# charger.net
KiCad netlist of a schematic drawn in EAGLE
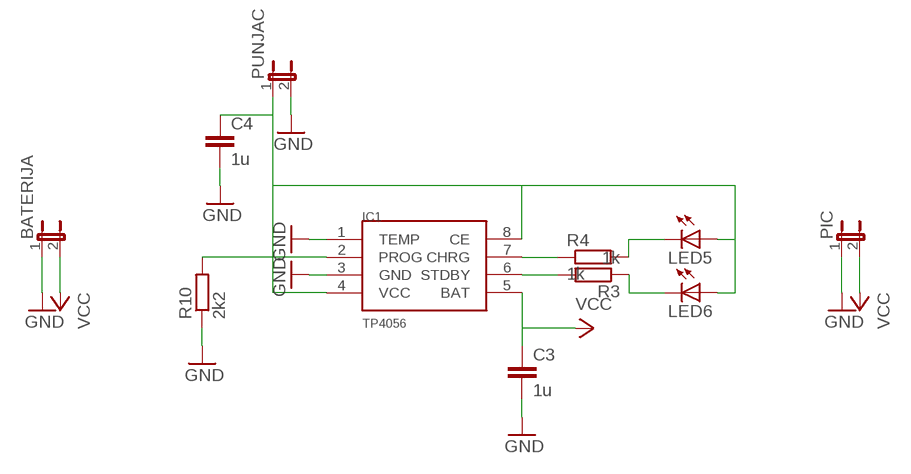
[diagram p0: schematic, sheet 1]

(export (version "E")
  (design (tool "Eeschema 10.0.6"))
  (components
    (comp (ref "BATERIJA")
      (value "JP1E")
      (footprint "eagle-import:JP1")
      (libsource (lib "eagle-import") (part "JP1E"))
    )
    (comp (ref "C3")
      (value "1u")
      (footprint "eagle-import:C050-024X044")
      (libsource (lib "eagle-import") (part "C-EU050-024X044"))
    )
    (comp (ref "C4")
      (value "1u")
      (footprint "eagle-import:C050-024X044")
      (libsource (lib "eagle-import") (part "C-EU050-024X044"))
    )
    (comp (ref "IC1")
      (value "TP4056")
      (footprint "eagle-import:SOP-8")
      (libsource (lib "eagle-import") (part "TP4056"))
    )
    (comp (ref "LED5")
      (value "LED3MM")
      (footprint "eagle-import:LED3MM")
      (libsource (lib "eagle-import") (part "LED3MM"))
    )
    (comp (ref "LED6")
      (value "LED3MM")
      (footprint "eagle-import:LED3MM")
      (libsource (lib "eagle-import") (part "LED3MM"))
    )
    (comp (ref "PIC")
      (value "JP1E")
      (footprint "eagle-import:JP1")
      (libsource (lib "eagle-import") (part "JP1E"))
    )
    (comp (ref "PUNJAC")
      (value "JP1E")
      (footprint "eagle-import:JP1")
      (libsource (lib "eagle-import") (part "JP1E"))
    )
    (comp (ref "R3")
      (value "1k")
      (footprint "eagle-import:0207_10")
      (libsource (lib "eagle-import") (part "R-EU_0207/10"))
    )
    (comp (ref "R4")
      (value "1k")
      (footprint "eagle-import:0207_10")
      (libsource (lib "eagle-import") (part "R-EU_0207/10"))
    )
    (comp (ref "R10")
      (value "2k2")
      (footprint "eagle-import:0207_10")
      (libsource (lib "eagle-import") (part "R-EU_0207/10"))
    )
  )
  (nets
    (net (code "1") (name "GND") (class "Default")
      (node (ref "BATERIJA") (pin "1") (pinfunction "1_1") (pintype "passive"))
      (node (ref "C3") (pin "2") (pinfunction "2_2") (pintype "passive"))
      (node (ref "C4") (pin "2") (pinfunction "2_2") (pintype "passive"))
      (node (ref "IC1") (pin "1") (pinfunction "TEMP_1") (pintype "bidirectional"))
      (node (ref "IC1") (pin "3") (pinfunction "GND_3") (pintype "bidirectional"))
      (node (ref "PIC") (pin "1") (pinfunction "1_1") (pintype "passive"))
      (node (ref "PUNJAC") (pin "2") (pinfunction "2_2") (pintype "passive"))
      (node (ref "R10") (pin "1") (pinfunction "1_1") (pintype "passive"))
    )
    (net (code "2") (name "Net-(IC1-CE)") (class "Default")
      (node (ref "C4") (pin "1") (pinfunction "1_1") (pintype "passive"))
      (node (ref "IC1") (pin "4") (pinfunction "VCC_4") (pintype "bidirectional"))
      (node (ref "IC1") (pin "8") (pinfunction "CE_8") (pintype "bidirectional"))
      (node (ref "LED5") (pin "A") (pinfunction "A_A") (pintype "passive"))
      (node (ref "LED6") (pin "A") (pinfunction "A_A") (pintype "passive"))
      (node (ref "PUNJAC") (pin "1") (pinfunction "1_1") (pintype "passive"))
    )
    (net (code "3") (name "Net-(IC1-CHRG)") (class "Default")
      (node (ref "IC1") (pin "7") (pinfunction "CHRG_7") (pintype "bidirectional"))
      (node (ref "R4") (pin "1") (pinfunction "1_1") (pintype "passive"))
    )
    (net (code "4") (name "Net-(IC1-PROG)") (class "Default")
      (node (ref "IC1") (pin "2") (pinfunction "PROG_2") (pintype "bidirectional"))
      (node (ref "R10") (pin "2") (pinfunction "2_2") (pintype "passive"))
    )
    (net (code "5") (name "Net-(IC1-STDBY)") (class "Default")
      (node (ref "IC1") (pin "6") (pinfunction "STDBY_6") (pintype "bidirectional"))
      (node (ref "R3") (pin "2") (pinfunction "2_2") (pintype "passive"))
    )
    (net (code "6") (name "Net-(LED5-C)") (class "Default")
      (node (ref "LED5") (pin "K") (pinfunction "C_K") (pintype "passive"))
      (node (ref "R4") (pin "2") (pinfunction "2_2") (pintype "passive"))
    )
    (net (code "7") (name "Net-(LED6-C)") (class "Default")
      (node (ref "LED6") (pin "K") (pinfunction "C_K") (pintype "passive"))
      (node (ref "R3") (pin "1") (pinfunction "1_1") (pintype "passive"))
    )
    (net (code "8") (name "VCC") (class "Default")
      (node (ref "BATERIJA") (pin "2") (pinfunction "2_2") (pintype "passive"))
      (node (ref "C3") (pin "1") (pinfunction "1_1") (pintype "passive"))
      (node (ref "IC1") (pin "5") (pinfunction "BAT_5") (pintype "bidirectional"))
      (node (ref "PIC") (pin "2") (pinfunction "2_2") (pintype "passive"))
    )
  )
)
